# Cansat2019_1516_Payload_SectionA_v01.net
KiCad netlist of a schematic drawn in EAGLE
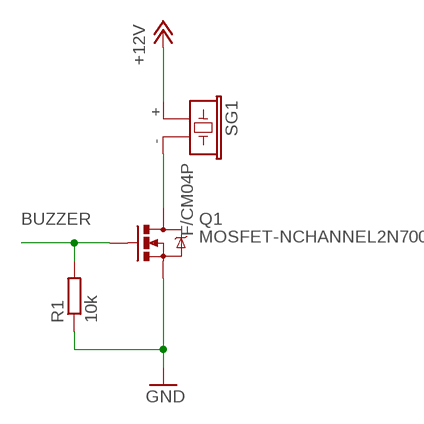
[diagram p0: schematic, sheet 1]

(export (version "E")
  (design (tool "Eeschema 10.0.6"))
  (components
    (comp (ref "Q1")
      (value "MOSFET-NCHANNEL2N7000")
      (footprint "eagle-import:TO-92")
      (libsource (lib "eagle-import") (part "MOSFET-NCHANNEL2N7000"))
    )
    (comp (ref "R1")
      (value "10k")
      (footprint "eagle-import:0204_7")
      (libsource (lib "eagle-import") (part "R-EU_0204/7"))
    )
    (comp (ref "SG1")
      (value "F/CM04P")
      (footprint "eagle-import:F_CM04P")
      (libsource (lib "eagle-import") (part "F/CM04P"))
    )
  )
  (nets
    (net (code "1") (name "+12V") (class "Default")
      (node (ref "SG1") (pin "+") (pinfunction "1_+") (pintype "passive"))
    )
    (net (code "2") (name "/BUZZER") (class "Default")
      (node (ref "Q1") (pin "2") (pinfunction "G_2") (pintype "passive"))
      (node (ref "R1") (pin "2") (pinfunction "2_2") (pintype "passive"))
    )
    (net (code "3") (name "GND") (class "Default")
      (node (ref "Q1") (pin "1") (pinfunction "S_1") (pintype "passive"))
      (node (ref "R1") (pin "1") (pinfunction "1_1") (pintype "passive"))
    )
    (net (code "4") (name "Net-(Q1-D)") (class "Default")
      (node (ref "Q1") (pin "3") (pinfunction "D_3") (pintype "passive"))
      (node (ref "SG1") (pin "-") (pinfunction "2_-") (pintype "passive"))
    )
  )
)
